# easySens-RS485-RND_455-00307-V002.net
KiCad netlist of a schematic drawn in EAGLE
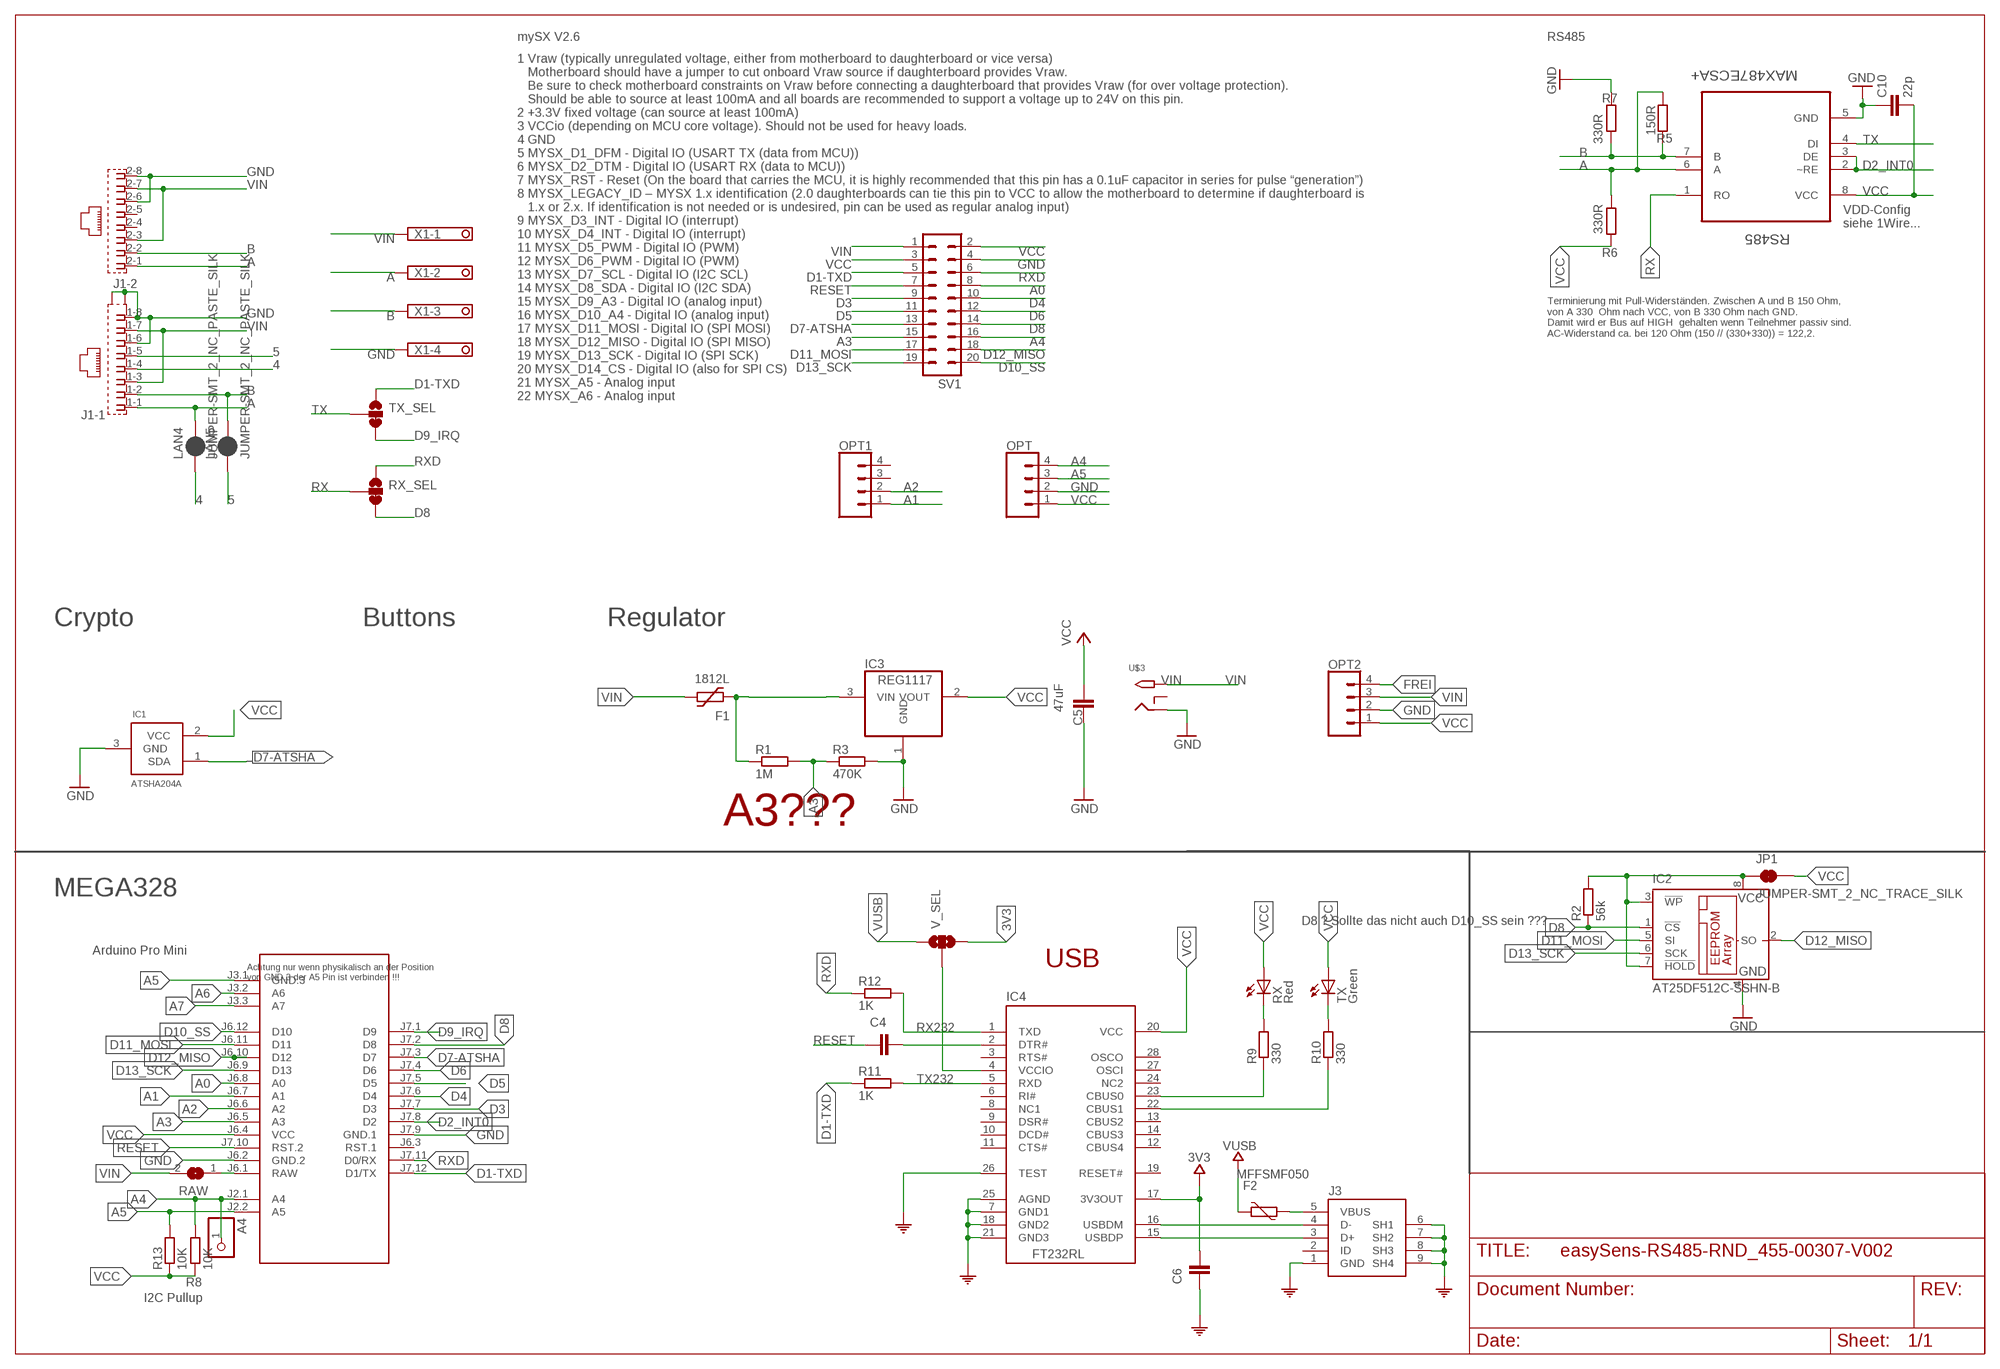
[diagram p0: schematic, sheet 1]

(export (version "E")
  (design (tool "Eeschema 10.0.6"))
  (components
    (comp (ref "A4")
      (value "PINHD-1X1")
      (footprint "eagle-import:1X01")
      (libsource (lib "eagle-import") (part "PINHD-1X1"))
    )
    (comp (ref "C4")
      (value "100nF")
      (footprint "eagle-import:C0805")
      (libsource (lib "eagle-import") (part "resistor@1_C-EUC0805"))
    )
    (comp (ref "C5")
      (value "47uF")
      (footprint "eagle-import:C1210")
      (libsource (lib "eagle-import") (part "C-EUC1210"))
    )
    (comp (ref "C6")
      (value "100nF")
      (footprint "eagle-import:C0805")
      (libsource (lib "eagle-import") (part "resistor@1_C-EUC0805"))
    )
    (comp (ref "C10")
      (value "22p")
      (footprint "eagle-import:C0805")
      (libsource (lib "eagle-import") (part "C-EUC0805"))
    )
    (comp (ref "F1")
      (value "1812L")
      (footprint "eagle-import:1812L")
      (libsource (lib "eagle-import") (part "1812L"))
    )
    (comp (ref "F2")
      (value "MFFSMF050")
      (footprint "eagle-import:0603-1608X90N")
      (fields (field (name "MANUFACTURER") "Bourns Inc "))
      (libsource (lib "eagle-import") (part "PTC"))
    )
    (comp (ref "IC1")
      (value "ATSHA204A")
      (footprint "eagle-import:SOT23")
      (libsource (lib "eagle-import") (part "ATSHA204A"))
    )
    (comp (ref "IC2")
      (value "AT25DF512C-SSHN-B")
      (footprint "eagle-import:SO-08")
      (fields (field (name "MF") "MICROCHIP") (field (name "MPN") "25AA080/SN"))
      (libsource (lib "eagle-import") (part "25SNAA080"))
    )
    (comp (ref "IC3")
      (value "REG1117")
      (footprint "eagle-import:SOT223")
      (libsource (lib "eagle-import") (part "REG1117"))
    )
    (comp (ref "IC4")
      (value "FT232RL")
      (footprint "eagle-import:SSOP28")
      (libsource (lib "eagle-import") (part "0226_FT232RL"))
    )
    (comp (ref "J1")
      (value "RJ45_2X_NARROW_SHILDPINS")
      (footprint "eagle-import:RJ45_2X_NARROW_SHILDPINS")
      (libsource (lib "eagle-import") (part "RJ45_2X_NARROW_SHILDPINS"))
    )
    (comp (ref "J3")
      (value "0219_14850")
      (footprint "eagle-import:USB-MINI-B_2")
      (fields (field (name "PART_NUMBER") "14850"))
      (libsource (lib "eagle-import") (part "0219_14850"))
    )
    (comp (ref "JP1")
      (value "JUMPER-SMT_2_NC_TRACE_SILK")
      (footprint "eagle-import:SMT-JUMPER_2_NC_TRACE_SILK")
      (libsource (lib "eagle-import") (part "JUMPER-SMT_2_NC_TRACE_SILK"))
    )
    (comp (ref "LAN4")
      (value "JUMPER-SMT_2_NC_PASTE_SILK")
      (footprint "eagle-import:SMT-JUMPER_2_NC_PASTE_SILK")
      (libsource (lib "eagle-import") (part "JUMPER-SMT_2_NC_PASTE_SILK"))
    )
    (comp (ref "LAN5")
      (value "JUMPER-SMT_2_NC_PASTE_SILK")
      (footprint "eagle-import:SMT-JUMPER_2_NC_PASTE_SILK")
      (libsource (lib "eagle-import") (part "JUMPER-SMT_2_NC_PASTE_SILK"))
    )
    (comp (ref "M1")
      (value "ARDUINO-PRO-MINI-3.3V#NP")
      (footprint "eagle-import:ARDUINO-PRO-MINI#NP")
      (libsource (lib "eagle-import") (part "ARDUINO-PRO-MINI-#NP3.3V"))
    )
    (comp (ref "OPT")
      (value "CONN_04")
      (footprint "eagle-import:1X04")
      (libsource (lib "eagle-import") (part "CONN_04"))
    )
    (comp (ref "OPT1")
      (value "CONN_04")
      (footprint "eagle-import:1X04")
      (libsource (lib "eagle-import") (part "CONN_04"))
    )
    (comp (ref "OPT2")
      (value "CONN_04")
      (footprint "eagle-import:1X04")
      (libsource (lib "eagle-import") (part "CONN_04"))
    )
    (comp (ref "R1")
      (value "1M")
      (footprint "eagle-import:M0805")
      (libsource (lib "eagle-import") (part "R-EU_M0805"))
    )
    (comp (ref "R2")
      (value "56k")
      (footprint "eagle-import:M0805")
      (libsource (lib "eagle-import") (part "resistor_R-EU_M0805"))
    )
    (comp (ref "R3")
      (value "470K")
      (footprint "eagle-import:R0805")
      (libsource (lib "eagle-import") (part "R-EU_R0805"))
    )
    (comp (ref "R5")
      (value "150R")
      (footprint "eagle-import:R0805")
      (libsource (lib "eagle-import") (part "R-EU_R0805"))
    )
    (comp (ref "R6")
      (value "330R")
      (footprint "eagle-import:R0805")
      (libsource (lib "eagle-import") (part "R-EU_R0805"))
    )
    (comp (ref "R7")
      (value "330R")
      (footprint "eagle-import:R0805")
      (libsource (lib "eagle-import") (part "R-EU_R0805"))
    )
    (comp (ref "R8")
      (value "10K")
      (footprint "eagle-import:R0805")
      (libsource (lib "eagle-import") (part "R-EU_R0805"))
    )
    (comp (ref "R9")
      (value "330")
      (footprint "eagle-import:R0805")
      (libsource (lib "eagle-import") (part "resistor@1_R-EU_R0805"))
    )
    (comp (ref "R10")
      (value "330")
      (footprint "eagle-import:R0805")
      (libsource (lib "eagle-import") (part "resistor@1_R-EU_R0805"))
    )
    (comp (ref "R11")
      (value "1K")
      (footprint "eagle-import:R0805")
      (libsource (lib "eagle-import") (part "resistor@1_R-EU_R0805"))
    )
    (comp (ref "R12")
      (value "1K")
      (footprint "eagle-import:R0805")
      (libsource (lib "eagle-import") (part "resistor@1_R-EU_R0805"))
    )
    (comp (ref "R13")
      (value "10K")
      (footprint "eagle-import:R0805")
      (libsource (lib "eagle-import") (part "R-EU_R0805"))
    )
    (comp (ref "RAW") (value "SJ") (footprint "eagle-import:SJ") (libsource (lib "eagle-import") (part "SJ")))
    (comp (ref "RS485")
      (value "MAX487ECSA+")
      (footprint "eagle-import:SOIC127P600X175-8N")
      (libsource (lib "eagle-import") (part "MAX487ECSA+"))
    )
    (comp (ref "RX")
      (value "Red")
      (footprint "eagle-import:CHIPLED_0805")
      (fields (field (name "PART_NUMBER") "KTP-2012SURCK"))
      (libsource (lib "eagle-import") (part "0181_KTP-2012SURCK"))
    )
    (comp (ref "RX_SEL")
      (value "JUMPER-SMT_3_1-NC_TRACE_SILK")
      (footprint "eagle-import:SMT-JUMPER_3_1-NC_TRACE_SILK")
      (libsource (lib "eagle-import") (part "JUMPER-SMT_3_1-NC_TRACE_SILK"))
    )
    (comp (ref "SV1")
      (value "MA10-2")
      (footprint "eagle-import:MA10-2")
      (libsource (lib "eagle-import") (part "MA10-2"))
    )
    (comp (ref "TX")
      (value "Green")
      (footprint "eagle-import:CHIPLED_0805")
      (fields (field (name "PART_NUMBER") "KPT-2012SGC"))
      (libsource (lib "eagle-import") (part "0043_KPT-2012SGC"))
    )
    (comp (ref "TX_SEL")
      (value "JUMPER-SMT_3_1-NC_TRACE_SILK")
      (footprint "eagle-import:SMT-JUMPER_3_1-NC_TRACE_SILK")
      (libsource (lib "eagle-import") (part "JUMPER-SMT_3_1-NC_TRACE_SILK"))
    )
    (comp (ref "U$3")
      (value "2.1MMJACKTHM")
      (footprint "eagle-import:PJ-102A")
      (libsource (lib "eagle-import") (part "2.1MMJACKTHM"))
    )
    (comp (ref "V_SEL")
      (value "JUMPER-SMT_3_NO_SILK")
      (footprint "eagle-import:SMT-JUMPER_3_NO_SILK")
      (libsource (lib "eagle-import") (part "JUMPER-SMT_3_NO_SILK"))
    )
    (comp (ref "X1")
      (value "1751264")
      (footprint "eagle-import:1751264")
      (libsource (lib "eagle-import") (part "1751264"))
    )
  )
  (nets
    (net (code "1") (name "/4") (class "Default")
      (node (ref "J1") (pin "1-4") (pinfunction "4_1-4") (pintype "passive"))
      (node (ref "LAN4") (pin "1") (pinfunction "1_1") (pintype "passive"))
    )
    (net (code "2") (name "/5") (class "Default")
      (node (ref "J1") (pin "1-5") (pinfunction "5_1-5") (pintype "passive"))
      (node (ref "LAN5") (pin "1") (pinfunction "1_1") (pintype "passive"))
    )
    (net (code "3") (name "/A") (class "Default")
      (node (ref "J1") (pin "1-1") (pinfunction "1_1-1") (pintype "passive"))
      (node (ref "J1") (pin "2-1") (pinfunction "1_2-1") (pintype "passive"))
      (node (ref "LAN4") (pin "2") (pinfunction "2_2") (pintype "passive"))
      (node (ref "R5") (pin "1") (pinfunction "1_1") (pintype "passive"))
      (node (ref "R6") (pin "2") (pinfunction "2_2") (pintype "passive"))
      (node (ref "RS485") (pin "6") (pinfunction "A_6") (pintype "bidirectional"))
      (node (ref "X1") (pin "2") (pinfunction "K_2") (pintype "passive"))
    )
    (net (code "4") (name "/B") (class "Default")
      (node (ref "J1") (pin "1-2") (pinfunction "2_1-2") (pintype "passive"))
      (node (ref "J1") (pin "2-2") (pinfunction "2_2-2") (pintype "passive"))
      (node (ref "LAN5") (pin "2") (pinfunction "2_2") (pintype "passive"))
      (node (ref "R5") (pin "2") (pinfunction "2_2") (pintype "passive"))
      (node (ref "R7") (pin "1") (pinfunction "1_1") (pintype "passive"))
      (node (ref "RS485") (pin "7") (pinfunction "B_7") (pintype "bidirectional"))
      (node (ref "X1") (pin "3") (pinfunction "K_3") (pintype "passive"))
    )
    (net (code "5") (name "/RX232") (class "Default")
      (node (ref "IC4") (pin "1") (pinfunction "TXD_1") (pintype "output"))
      (node (ref "R12") (pin "2") (pinfunction "2_2") (pintype "passive"))
    )
    (net (code "6") (name "/TX") (class "Default")
      (node (ref "RS485") (pin "4") (pinfunction "DI_4") (pintype "input"))
      (node (ref "TX_SEL") (pin "2") (pinfunction "2_2") (pintype "passive"))
    )
    (net (code "7") (name "/TX232") (class "Default")
      (node (ref "IC4") (pin "5") (pinfunction "RXD_5") (pintype "input"))
      (node (ref "R11") (pin "2") (pinfunction "2_2") (pintype "passive"))
    )
    (net (code "8") (name "3V3") (class "Default")
      (node (ref "C6") (pin "2") (pinfunction "2_2") (pintype "passive"))
      (node (ref "IC4") (pin "17") (pinfunction "3V3OUT_17") (pintype "power_in"))
      (node (ref "V_SEL") (pin "3") (pinfunction "3_3") (pintype "passive"))
    )
    (net (code "9") (name "A0") (class "Default")
      (node (ref "M1") (pin "J6.8") (pinfunction "A0_J6.8") (pintype "bidirectional"))
      (node (ref "SV1") (pin "8") (pinfunction "8_8") (pintype "passive"))
    )
    (net (code "10") (name "A1") (class "Default")
      (node (ref "M1") (pin "J6.7") (pinfunction "A1_J6.7") (pintype "bidirectional"))
      (node (ref "OPT1") (pin "1") (pinfunction "1_1") (pintype "passive"))
    )
    (net (code "11") (name "A2") (class "Default")
      (node (ref "M1") (pin "J6.6") (pinfunction "A2_J6.6") (pintype "bidirectional"))
      (node (ref "OPT1") (pin "2") (pinfunction "2_2") (pintype "passive"))
    )
    (net (code "12") (name "A3") (class "Default")
      (node (ref "M1") (pin "J6.5") (pinfunction "A3_J6.5") (pintype "bidirectional"))
      (node (ref "R1") (pin "2") (pinfunction "2_2") (pintype "passive"))
      (node (ref "R3") (pin "1") (pinfunction "1_1") (pintype "passive"))
      (node (ref "SV1") (pin "15") (pinfunction "15_15") (pintype "passive"))
    )
    (net (code "13") (name "A4") (class "Default")
      (node (ref "A4") (pin "1") (pinfunction "1_1") (pintype "passive"))
      (node (ref "M1") (pin "J2.1") (pinfunction "A4_J2.1") (pintype "bidirectional"))
      (node (ref "OPT") (pin "4") (pinfunction "4_4") (pintype "passive"))
      (node (ref "R8") (pin "2") (pinfunction "2_2") (pintype "passive"))
      (node (ref "SV1") (pin "16") (pinfunction "16_16") (pintype "passive"))
    )
    (net (code "14") (name "A5") (class "Default")
      (node (ref "M1") (pin "J2.2") (pinfunction "A5_J2.2") (pintype "bidirectional"))
      (node (ref "M1") (pin "J3.1") (pinfunction "GND.3_J3.1") (pintype "bidirectional"))
      (node (ref "OPT") (pin "3") (pinfunction "3_3") (pintype "passive"))
      (node (ref "R13") (pin "2") (pinfunction "2_2") (pintype "passive"))
    )
    (net (code "15") (name "A6") (class "Default")
      (node (ref "M1") (pin "J3.2") (pinfunction "A6_J3.2") (pintype "bidirectional"))
    )
    (net (code "16") (name "A7") (class "Default")
      (node (ref "M1") (pin "J3.3") (pinfunction "A7_J3.3") (pintype "bidirectional"))
    )
    (net (code "17") (name "COM") (class "Default")
      (node (ref "C6") (pin "1") (pinfunction "1_1") (pintype "passive"))
      (node (ref "IC4") (pin "18") (pinfunction "GND2_18") (pintype "power_in"))
      (node (ref "IC4") (pin "21") (pinfunction "GND3_21") (pintype "power_in"))
      (node (ref "IC4") (pin "25") (pinfunction "AGND_25") (pintype "power_in"))
      (node (ref "IC4") (pin "26") (pinfunction "TEST_26") (pintype "bidirectional"))
      (node (ref "IC4") (pin "7") (pinfunction "GND1_7") (pintype "power_in"))
      (node (ref "J3") (pin "1") (pinfunction "GND_1") (pintype "passive"))
      (node (ref "J3") (pin "6") (pinfunction "SH1_6") (pintype "passive"))
      (node (ref "J3") (pin "7") (pinfunction "SH2_7") (pintype "passive"))
      (node (ref "J3") (pin "8") (pinfunction "SH3_8") (pintype "passive"))
      (node (ref "J3") (pin "9") (pinfunction "SH4_9") (pintype "passive"))
    )
    (net (code "18") (name "D1-TXD") (class "Default")
      (node (ref "M1") (pin "J7.12") (pinfunction "D1/TX_J7.12") (pintype "bidirectional"))
      (node (ref "R11") (pin "1") (pinfunction "1_1") (pintype "passive"))
      (node (ref "SV1") (pin "5") (pinfunction "5_5") (pintype "passive"))
      (node (ref "TX_SEL") (pin "1") (pinfunction "1_1") (pintype "passive"))
    )
    (net (code "19") (name "D2_INT0") (class "Default")
      (node (ref "M1") (pin "J7.8") (pinfunction "D2_J7.8") (pintype "bidirectional"))
      (node (ref "RS485") (pin "2") (pinfunction "~{RE}_2") (pintype "input"))
      (node (ref "RS485") (pin "3") (pinfunction "DE_3") (pintype "input"))
    )
    (net (code "20") (name "D3") (class "Default")
      (node (ref "M1") (pin "J7.7") (pinfunction "D3_J7.7") (pintype "bidirectional"))
      (node (ref "SV1") (pin "9") (pinfunction "9_9") (pintype "passive"))
    )
    (net (code "21") (name "D4") (class "Default")
      (node (ref "M1") (pin "J7.6") (pinfunction "D4_J7.6") (pintype "bidirectional"))
      (node (ref "SV1") (pin "10") (pinfunction "10_10") (pintype "passive"))
    )
    (net (code "22") (name "D5") (class "Default")
      (node (ref "M1") (pin "J7.5") (pinfunction "D5_J7.5") (pintype "bidirectional"))
      (node (ref "SV1") (pin "11") (pinfunction "11_11") (pintype "passive"))
    )
    (net (code "23") (name "D6") (class "Default")
      (node (ref "M1") (pin "J7.4") (pinfunction "D6_J7.4") (pintype "bidirectional"))
      (node (ref "SV1") (pin "12") (pinfunction "12_12") (pintype "passive"))
    )
    (net (code "24") (name "D7-ATSHA") (class "Default")
      (node (ref "IC1") (pin "1") (pinfunction "SDA_1") (pintype "bidirectional"))
      (node (ref "M1") (pin "J7.3") (pinfunction "D7_J7.3") (pintype "bidirectional"))
      (node (ref "SV1") (pin "13") (pinfunction "13_13") (pintype "passive"))
    )
    (net (code "25") (name "D8") (class "Default")
      (node (ref "IC2") (pin "1") (pinfunction "~{CS}_1") (pintype "input"))
      (node (ref "M1") (pin "J7.2") (pinfunction "D8_J7.2") (pintype "bidirectional"))
      (node (ref "R2") (pin "1") (pinfunction "1_1") (pintype "passive"))
      (node (ref "RX_SEL") (pin "3") (pinfunction "3_3") (pintype "passive"))
      (node (ref "SV1") (pin "14") (pinfunction "14_14") (pintype "passive"))
    )
    (net (code "26") (name "D9_IRQ") (class "Default")
      (node (ref "M1") (pin "J7.1") (pinfunction "D9_J7.1") (pintype "bidirectional"))
      (node (ref "TX_SEL") (pin "3") (pinfunction "3_3") (pintype "passive"))
    )
    (net (code "27") (name "D10_SS") (class "Default")
      (node (ref "M1") (pin "J6.12") (pinfunction "D10_J6.12") (pintype "bidirectional"))
      (node (ref "SV1") (pin "20") (pinfunction "20_20") (pintype "passive"))
    )
    (net (code "28") (name "D11_MOSI") (class "Default")
      (node (ref "IC2") (pin "5") (pinfunction "SI_5") (pintype "input"))
      (node (ref "M1") (pin "J6.11") (pinfunction "D11_J6.11") (pintype "bidirectional"))
      (node (ref "SV1") (pin "17") (pinfunction "17_17") (pintype "passive"))
    )
    (net (code "29") (name "D12_MISO") (class "Default")
      (node (ref "IC2") (pin "2") (pinfunction "SO_2") (pintype "bidirectional"))
      (node (ref "M1") (pin "J6.10") (pinfunction "D12_J6.10") (pintype "bidirectional"))
      (node (ref "SV1") (pin "18") (pinfunction "18_18") (pintype "passive"))
    )
    (net (code "30") (name "D13_SCK") (class "Default")
      (node (ref "IC2") (pin "6") (pinfunction "SCK_6") (pintype "input"))
      (node (ref "M1") (pin "J6.9") (pinfunction "D13_J6.9") (pintype "bidirectional"))
      (node (ref "SV1") (pin "19") (pinfunction "19_19") (pintype "passive"))
    )
    (net (code "31") (name "FREI") (class "Default")
      (node (ref "OPT2") (pin "4") (pinfunction "4_4") (pintype "passive"))
    )
    (net (code "32") (name "GND") (class "Default")
      (node (ref "C10") (pin "1") (pinfunction "1_1") (pintype "passive"))
      (node (ref "C5") (pin "1") (pinfunction "1_1") (pintype "passive"))
      (node (ref "IC1") (pin "3") (pinfunction "GND_3") (pintype "bidirectional"))
      (node (ref "IC2") (pin "4") (pinfunction "GND_4") (pintype "power_in"))
      (node (ref "IC3") (pin "1") (pinfunction "GND_1") (pintype "power_in"))
      (node (ref "J1") (pin "1-6") (pinfunction "6_1-6") (pintype "passive"))
      (node (ref "J1") (pin "1-8") (pinfunction "8_1-8") (pintype "passive"))
      (node (ref "J1") (pin "2-6") (pinfunction "6_2-6") (pintype "passive"))
      (node (ref "J1") (pin "2-8") (pinfunction "8_2-8") (pintype "passive"))
      (node (ref "J1") (pin "G1") (pinfunction "S1_G1") (pintype "passive"))
      (node (ref "J1") (pin "G3") (pinfunction "S2_G3") (pintype "passive"))
      (node (ref "M1") (pin "J6.2") (pinfunction "GND.2_J6.2") (pintype "power_in"))
      (node (ref "M1") (pin "J7.9") (pinfunction "GND.1_J7.9") (pintype "power_in"))
      (node (ref "OPT") (pin "2") (pinfunction "2_2") (pintype "passive"))
      (node (ref "OPT2") (pin "2") (pinfunction "2_2") (pintype "passive"))
      (node (ref "R3") (pin "2") (pinfunction "2_2") (pintype "passive"))
      (node (ref "R7") (pin "2") (pinfunction "2_2") (pintype "passive"))
      (node (ref "RS485") (pin "5") (pinfunction "GND_5") (pintype "passive"))
      (node (ref "SV1") (pin "4") (pinfunction "4_4") (pintype "passive"))
      (node (ref "U$3") (pin "RING") (pinfunction "RING_RING") (pintype "bidirectional"))
      (node (ref "X1") (pin "4") (pinfunction "K_4") (pintype "passive"))
    )
    (net (code "33") (name "Net-(F1-1)") (class "Default")
      (node (ref "F1") (pin "P$1") (pinfunction "1_P$1") (pintype "passive"))
      (node (ref "IC3") (pin "3") (pinfunction "VIN_3") (pintype "input"))
      (node (ref "R1") (pin "1") (pinfunction "1_1") (pintype "passive"))
    )
    (net (code "34") (name "Net-(IC2-VCC)") (class "Default")
      (node (ref "IC2") (pin "3") (pinfunction "~{WP}_3") (pintype "input"))
      (node (ref "IC2") (pin "7") (pinfunction "~{HOLD}_7") (pintype "input"))
      (node (ref "IC2") (pin "8") (pinfunction "VCC_8") (pintype "power_in"))
      (node (ref "JP1") (pin "1") (pinfunction "1_1") (pintype "passive"))
      (node (ref "R2") (pin "2") (pinfunction "2_2") (pintype "passive"))
    )
    (net (code "35") (name "Net-(IC4-CBUS0)") (class "Default")
      (node (ref "IC4") (pin "23") (pinfunction "CBUS0_23") (pintype "bidirectional"))
      (node (ref "R9") (pin "1") (pinfunction "1_1") (pintype "passive"))
    )
    (net (code "36") (name "Net-(IC4-CBUS1)") (class "Default")
      (node (ref "IC4") (pin "22") (pinfunction "CBUS1_22") (pintype "bidirectional"))
      (node (ref "R10") (pin "1") (pinfunction "1_1") (pintype "passive"))
    )
    (net (code "37") (name "Net-(IC4-DTR#)") (class "Default")
      (node (ref "C4") (pin "2") (pinfunction "2_2") (pintype "passive"))
      (node (ref "IC4") (pin "2") (pinfunction "DTR#_2") (pintype "output"))
    )
    (net (code "38") (name "Net-(IC4-USBDM)") (class "Default")
      (node (ref "IC4") (pin "16") (pinfunction "USBDM_16") (pintype "bidirectional"))
      (node (ref "J3") (pin "4") (pinfunction "D-_4") (pintype "bidirectional"))
    )
    (net (code "39") (name "Net-(IC4-USBDP)") (class "Default")
      (node (ref "IC4") (pin "15") (pinfunction "USBDP_15") (pintype "bidirectional"))
      (node (ref "J3") (pin "3") (pinfunction "D+_3") (pintype "bidirectional"))
    )
    (net (code "40") (name "Net-(IC4-VCCIO)") (class "Default")
      (node (ref "IC4") (pin "4") (pinfunction "VCCIO_4") (pintype "power_in"))
      (node (ref "V_SEL") (pin "2") (pinfunction "2_2") (pintype "passive"))
    )
    (net (code "41") (name "Net-(J3-VBUS)") (class "Default")
      (node (ref "F2") (pin "2") (pinfunction "2_2") (pintype "passive"))
      (node (ref "J3") (pin "5") (pinfunction "VBUS_5") (pintype "power_in"))
    )
    (net (code "42") (name "Net-(M1-RAW)") (class "Default")
      (node (ref "M1") (pin "J6.1") (pinfunction "RAW_J6.1") (pintype "power_in"))
      (node (ref "RAW") (pin "1") (pinfunction "1_1") (pintype "passive"))
    )
    (net (code "43") (name "Net-(R9-Pad2)") (class "Default")
      (node (ref "R9") (pin "2") (pinfunction "2_2") (pintype "passive"))
      (node (ref "RX") (pin "C") (pinfunction "C_C") (pintype "passive"))
    )
    (net (code "44") (name "Net-(R10-Pad2)") (class "Default")
      (node (ref "R10") (pin "2") (pinfunction "2_2") (pintype "passive"))
      (node (ref "TX") (pin "C") (pinfunction "C_C") (pintype "passive"))
    )
    (net (code "45") (name "RESET") (class "Default")
      (node (ref "C4") (pin "1") (pinfunction "1_1") (pintype "passive"))
      (node (ref "M1") (pin "J7.10") (pinfunction "RST.2_J7.10") (pintype "bidirectional"))
      (node (ref "SV1") (pin "7") (pinfunction "7_7") (pintype "passive"))
    )
    (net (code "46") (name "RX") (class "Default")
      (node (ref "RS485") (pin "1") (pinfunction "RO_1") (pintype "output"))
      (node (ref "RX_SEL") (pin "2") (pinfunction "2_2") (pintype "passive"))
    )
    (net (code "47") (name "RXD") (class "Default")
      (node (ref "M1") (pin "J7.11") (pinfunction "D0/RX_J7.11") (pintype "bidirectional"))
      (node (ref "R12") (pin "1") (pinfunction "1_1") (pintype "passive"))
      (node (ref "RX_SEL") (pin "1") (pinfunction "1_1") (pintype "passive"))
      (node (ref "SV1") (pin "6") (pinfunction "6_6") (pintype "passive"))
    )
    (net (code "48") (name "VCC") (class "Default")
      (node (ref "C10") (pin "2") (pinfunction "2_2") (pintype "passive"))
      (node (ref "C5") (pin "2") (pinfunction "2_2") (pintype "passive"))
      (node (ref "IC1") (pin "2") (pinfunction "VCC_2") (pintype "bidirectional"))
      (node (ref "IC3") (pin "2") (pinfunction "VOUT_2") (pintype "output"))
      (node (ref "IC4") (pin "20") (pinfunction "VCC_20") (pintype "power_in"))
      (node (ref "JP1") (pin "2") (pinfunction "2_2") (pintype "passive"))
      (node (ref "M1") (pin "J6.4") (pinfunction "VCC_J6.4") (pintype "power_in"))
      (node (ref "OPT") (pin "1") (pinfunction "1_1") (pintype "passive"))
      (node (ref "OPT2") (pin "1") (pinfunction "1_1") (pintype "passive"))
      (node (ref "R13") (pin "1") (pinfunction "1_1") (pintype "passive"))
      (node (ref "R6") (pin "1") (pinfunction "1_1") (pintype "passive"))
      (node (ref "R8") (pin "1") (pinfunction "1_1") (pintype "passive"))
      (node (ref "RS485") (pin "8") (pinfunction "VCC_8") (pintype "power_in"))
      (node (ref "RX") (pin "A") (pinfunction "A_A") (pintype "passive"))
      (node (ref "SV1") (pin "2") (pinfunction "2_2") (pintype "passive"))
      (node (ref "SV1") (pin "3") (pinfunction "3_3") (pintype "passive"))
      (node (ref "TX") (pin "A") (pinfunction "A_A") (pintype "passive"))
    )
    (net (code "49") (name "VIN") (class "Default")
      (node (ref "F1") (pin "P$2") (pinfunction "2_P$2") (pintype "passive"))
      (node (ref "J1") (pin "1-3") (pinfunction "3_1-3") (pintype "passive"))
      (node (ref "J1") (pin "1-7") (pinfunction "7_1-7") (pintype "passive"))
      (node (ref "J1") (pin "2-3") (pinfunction "3_2-3") (pintype "passive"))
      (node (ref "J1") (pin "2-7") (pinfunction "7_2-7") (pintype "passive"))
      (node (ref "OPT2") (pin "3") (pinfunction "3_3") (pintype "passive"))
      (node (ref "RAW") (pin "2") (pinfunction "2_2") (pintype "passive"))
      (node (ref "SV1") (pin "1") (pinfunction "1_1") (pintype "passive"))
      (node (ref "U$3") (pin "TIP") (pinfunction "TIP_TIP") (pintype "bidirectional"))
      (node (ref "X1") (pin "1") (pinfunction "K_1") (pintype "passive"))
    )
    (net (code "50") (name "VUSB") (class "Default")
      (node (ref "F2") (pin "1") (pinfunction "1_1") (pintype "passive"))
      (node (ref "V_SEL") (pin "1") (pinfunction "1_1") (pintype "passive"))
    )
    (net (code "51") (name "unconnected-(IC4-CBUS2-Pad13)") (class "Default")
      (node (ref "IC4") (pin "13") (pinfunction "CBUS2_13") (pintype "bidirectional"))
    )
    (net (code "52") (name "unconnected-(IC4-CBUS3-Pad14)") (class "Default")
      (node (ref "IC4") (pin "14") (pinfunction "CBUS3_14") (pintype "bidirectional"))
    )
    (net (code "53") (name "unconnected-(IC4-CBUS4-Pad12)") (class "Default")
      (node (ref "IC4") (pin "12") (pinfunction "CBUS4_12") (pintype "bidirectional"))
    )
    (net (code "54") (name "unconnected-(IC4-CTS#-Pad11)") (class "Default")
      (node (ref "IC4") (pin "11") (pinfunction "CTS#_11") (pintype "bidirectional"))
    )
    (net (code "55") (name "unconnected-(IC4-DCD#-Pad10)") (class "Default")
      (node (ref "IC4") (pin "10") (pinfunction "DCD#_10") (pintype "bidirectional"))
    )
    (net (code "56") (name "unconnected-(IC4-DSR#-Pad9)") (class "Default")
      (node (ref "IC4") (pin "9") (pinfunction "DSR#_9") (pintype "bidirectional"))
    )
    (net (code "57") (name "unconnected-(IC4-NC1-Pad8)") (class "Default")
      (node (ref "IC4") (pin "8") (pinfunction "NC1_8") (pintype "bidirectional"))
    )
    (net (code "58") (name "unconnected-(IC4-NC2-Pad24)") (class "Default")
      (node (ref "IC4") (pin "24") (pinfunction "NC2_24") (pintype "no_connect"))
    )
    (net (code "59") (name "unconnected-(IC4-OSCI-Pad27)") (class "Default")
      (node (ref "IC4") (pin "27") (pinfunction "OSCI_27") (pintype "bidirectional"))
    )
    (net (code "60") (name "unconnected-(IC4-OSCO-Pad28)") (class "Default")
      (node (ref "IC4") (pin "28") (pinfunction "OSCO_28") (pintype "output"))
    )
    (net (code "61") (name "unconnected-(IC4-RESET#-Pad19)") (class "Default")
      (node (ref "IC4") (pin "19") (pinfunction "RESET#_19") (pintype "bidirectional"))
    )
    (net (code "62") (name "unconnected-(IC4-RI#-Pad6)") (class "Default")
      (node (ref "IC4") (pin "6") (pinfunction "RI#_6") (pintype "bidirectional"))
    )
    (net (code "63") (name "unconnected-(IC4-RTS#-Pad3)") (class "Default")
      (node (ref "IC4") (pin "3") (pinfunction "RTS#_3") (pintype "output"))
    )
    (net (code "64") (name "unconnected-(J1B-4-Pad2-4)") (class "Default")
      (node (ref "J1") (pin "2-4") (pinfunction "4_2-4") (pintype "passive"))
    )
    (net (code "65") (name "unconnected-(J1B-5-Pad2-5)") (class "Default")
      (node (ref "J1") (pin "2-5") (pinfunction "5_2-5") (pintype "passive"))
    )
    (net (code "66") (name "unconnected-(J3-ID-Pad2)") (class "Default")
      (node (ref "J3") (pin "2") (pinfunction "ID_2") (pintype "bidirectional"))
    )
    (net (code "67") (name "unconnected-(M1-RST.1-PadJ6.3)") (class "Default")
      (node (ref "M1") (pin "J6.3") (pinfunction "RST.1_J6.3") (pintype "bidirectional"))
    )
    (net (code "68") (name "unconnected-(OPT1-Pad3)") (class "Default")
      (node (ref "OPT1") (pin "3") (pinfunction "3_3") (pintype "passive"))
    )
    (net (code "69") (name "unconnected-(OPT1-Pad4)") (class "Default")
      (node (ref "OPT1") (pin "4") (pinfunction "4_4") (pintype "passive"))
    )
    (net (code "70") (name "unconnected-(U$3-PadRING_SW)") (class "Default")
      (node (ref "U$3") (pin "RING_SW") (pinfunction "RING_SW_RING_SW") (pintype "bidirectional"))
    )
  )
)
